# transistor-BSS806N.net
KiCad netlist of a schematic drawn in EAGLE
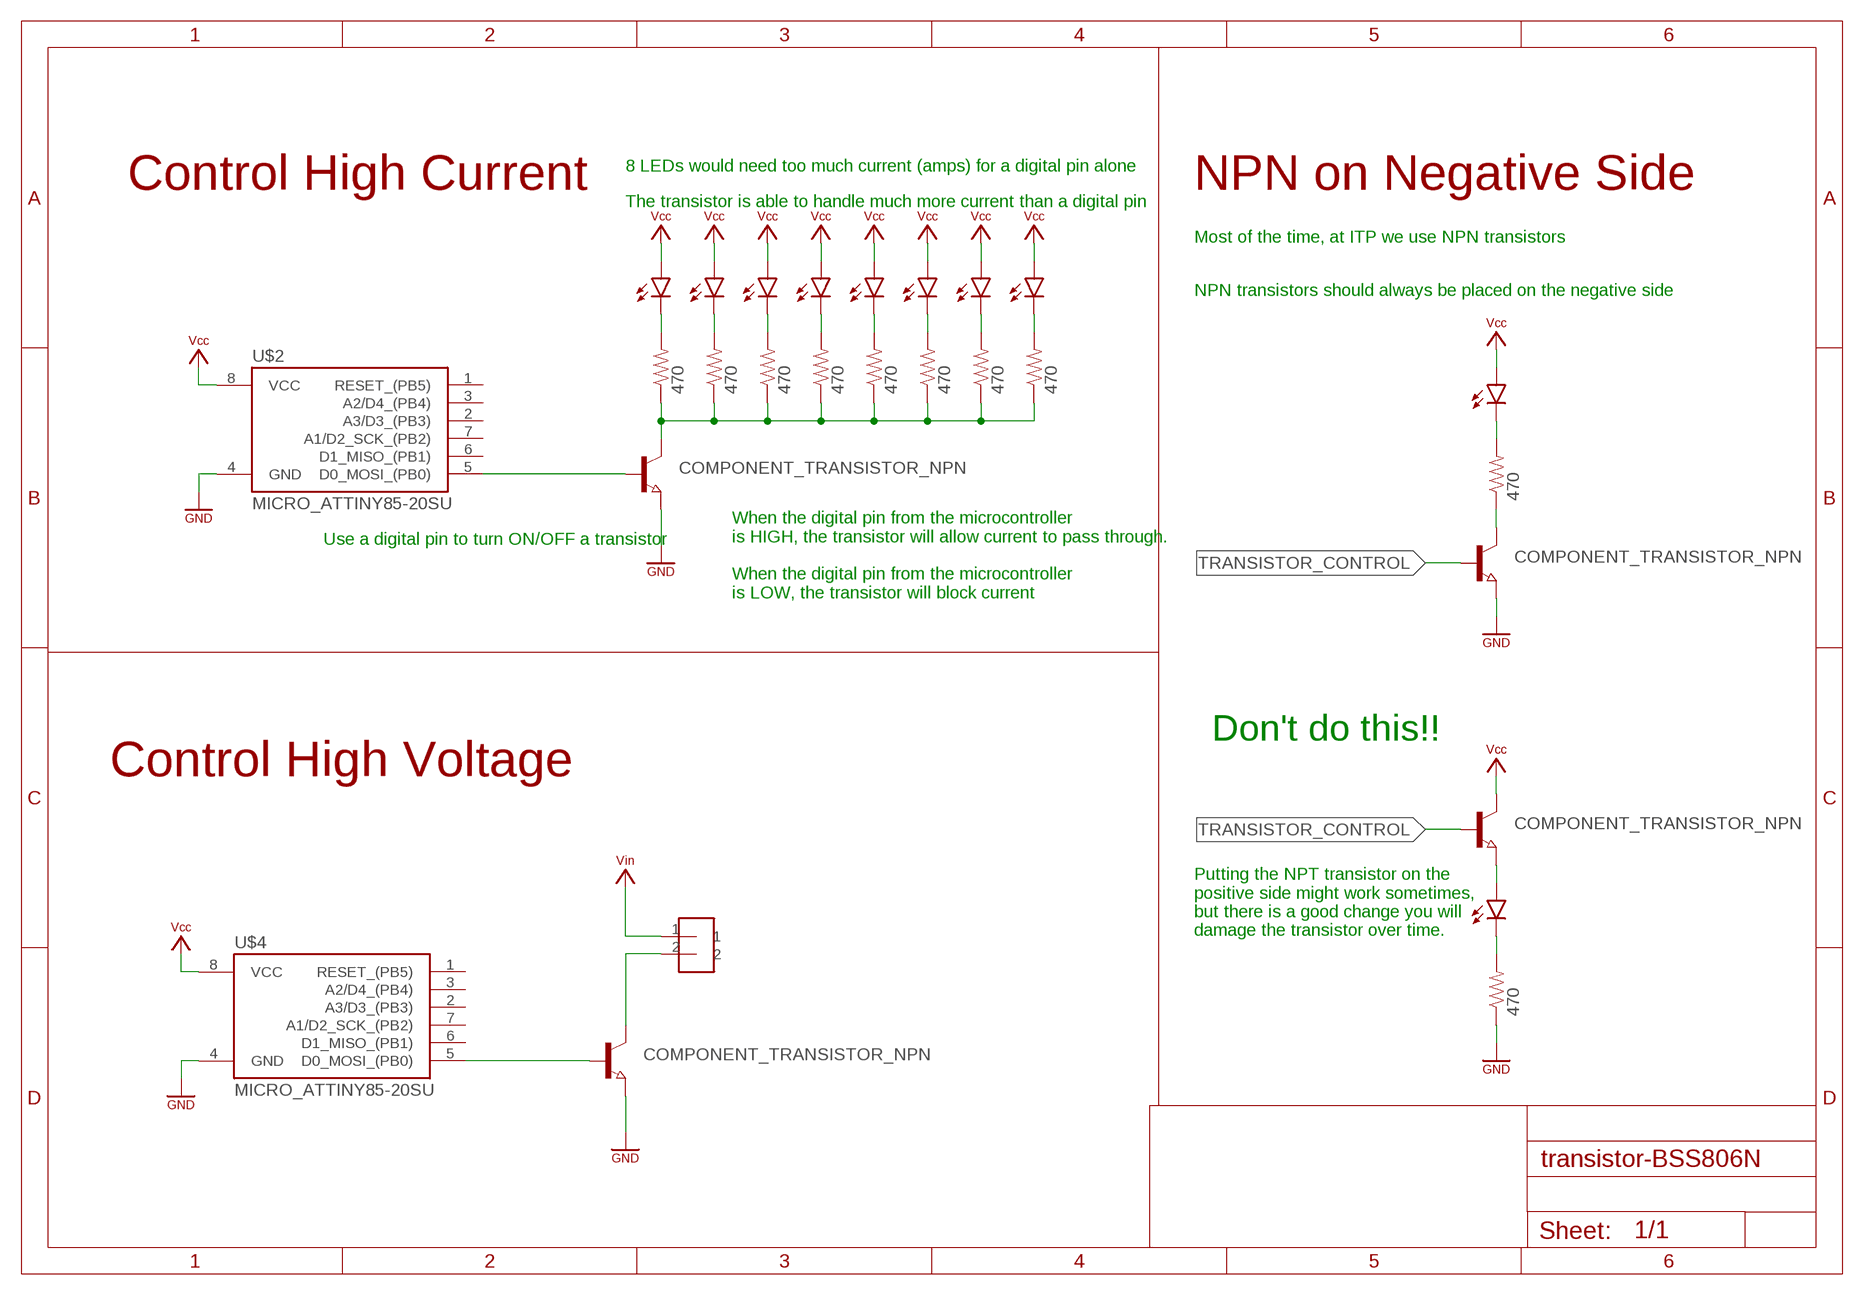
[diagram p0: schematic, sheet 1]

(export (version "E")
  (design (tool "Eeschema 10.0.6"))
  (components
    (comp (ref "LED1")
      (value "LED-0805")
      (footprint "eagle-import:CHIP-LED0805")
      (libsource (lib "eagle-import") (part "LED-0805"))
    )
    (comp (ref "LED2")
      (value "LED-0805")
      (footprint "eagle-import:CHIP-LED0805")
      (libsource (lib "eagle-import") (part "LED-0805"))
    )
    (comp (ref "LED3")
      (value "LED-0805")
      (footprint "eagle-import:CHIP-LED0805")
      (libsource (lib "eagle-import") (part "LED-0805"))
    )
    (comp (ref "LED4")
      (value "LED-0805")
      (footprint "eagle-import:CHIP-LED0805")
      (libsource (lib "eagle-import") (part "LED-0805"))
    )
    (comp (ref "LED5")
      (value "LED-0805")
      (footprint "eagle-import:CHIP-LED0805")
      (libsource (lib "eagle-import") (part "LED-0805"))
    )
    (comp (ref "LED6")
      (value "LED-0805")
      (footprint "eagle-import:CHIP-LED0805")
      (libsource (lib "eagle-import") (part "LED-0805"))
    )
    (comp (ref "LED7")
      (value "LED-0805")
      (footprint "eagle-import:CHIP-LED0805")
      (libsource (lib "eagle-import") (part "LED-0805"))
    )
    (comp (ref "LED8")
      (value "LED-0805")
      (footprint "eagle-import:CHIP-LED0805")
      (libsource (lib "eagle-import") (part "LED-0805"))
    )
    (comp (ref "LED9")
      (value "LED-0805")
      (footprint "eagle-import:CHIP-LED0805")
      (libsource (lib "eagle-import") (part "LED-0805"))
    )
    (comp (ref "LED10")
      (value "LED-0805")
      (footprint "eagle-import:CHIP-LED0805")
      (libsource (lib "eagle-import") (part "LED-0805"))
    )
    (comp (ref "R1")
      (value "470")
      (footprint "eagle-import:0805")
      (libsource (lib "eagle-import") (part "COMPONENT_RESISTOR-0805"))
    )
    (comp (ref "R2")
      (value "470")
      (footprint "eagle-import:0805")
      (libsource (lib "eagle-import") (part "COMPONENT_RESISTOR-0805"))
    )
    (comp (ref "R3")
      (value "470")
      (footprint "eagle-import:0805")
      (libsource (lib "eagle-import") (part "COMPONENT_RESISTOR-0805"))
    )
    (comp (ref "R4")
      (value "470")
      (footprint "eagle-import:0805")
      (libsource (lib "eagle-import") (part "COMPONENT_RESISTOR-0805"))
    )
    (comp (ref "R5")
      (value "470")
      (footprint "eagle-import:0805")
      (libsource (lib "eagle-import") (part "COMPONENT_RESISTOR-0805"))
    )
    (comp (ref "R6")
      (value "470")
      (footprint "eagle-import:0805")
      (libsource (lib "eagle-import") (part "COMPONENT_RESISTOR-0805"))
    )
    (comp (ref "R7")
      (value "470")
      (footprint "eagle-import:0805")
      (libsource (lib "eagle-import") (part "COMPONENT_RESISTOR-0805"))
    )
    (comp (ref "R8")
      (value "470")
      (footprint "eagle-import:0805")
      (libsource (lib "eagle-import") (part "COMPONENT_RESISTOR-0805"))
    )
    (comp (ref "R9")
      (value "470")
      (footprint "eagle-import:0805")
      (libsource (lib "eagle-import") (part "COMPONENT_RESISTOR-0805"))
    )
    (comp (ref "R10")
      (value "470")
      (footprint "eagle-import:0805")
      (libsource (lib "eagle-import") (part "COMPONENT_RESISTOR-0805"))
    )
    (comp (ref "U$1")
      (value "COMPONENT_TRANSISTOR_NPN")
      (footprint "eagle-import:SOT23")
      (libsource (lib "eagle-import") (part "COMPONENT_TRANSISTOR_NPN"))
    )
    (comp (ref "U$2")
      (value "MICRO_ATTINY85-20SU")
      (footprint "eagle-import:SOIC8")
      (libsource (lib "eagle-import") (part "MICRO_ATTINY85-20SU"))
    )
    (comp (ref "U$3")
      (value "COMPONENT_TRANSISTOR_NPN")
      (footprint "eagle-import:SOT23")
      (libsource (lib "eagle-import") (part "COMPONENT_TRANSISTOR_NPN"))
    )
    (comp (ref "U$4")
      (value "MICRO_ATTINY85-20SU")
      (footprint "eagle-import:SOIC8")
      (libsource (lib "eagle-import") (part "MICRO_ATTINY85-20SU"))
    )
    (comp (ref "U$5")
      (value "CONN_SCREW_TERMINAL")
      (footprint "eagle-import:691508110302")
      (libsource (lib "eagle-import") (part "CONN_SCREW_TERMINAL"))
    )
    (comp (ref "U$7")
      (value "COMPONENT_TRANSISTOR_NPN")
      (footprint "eagle-import:SOT23")
      (libsource (lib "eagle-import") (part "COMPONENT_TRANSISTOR_NPN"))
    )
    (comp (ref "U$8")
      (value "COMPONENT_TRANSISTOR_NPN")
      (footprint "eagle-import:SOT23")
      (libsource (lib "eagle-import") (part "COMPONENT_TRANSISTOR_NPN"))
    )
  )
  (nets
    (net (code "1") (name "Net-(LED1-PadC)") (class "Default")
      (node (ref "LED1") (pin "C") (pinfunction "C_C") (pintype "passive"))
      (node (ref "R1") (pin "2") (pinfunction "2_2") (pintype "passive"))
    )
    (net (code "2") (name "Net-(LED2-PadC)") (class "Default")
      (node (ref "LED2") (pin "C") (pinfunction "C_C") (pintype "passive"))
      (node (ref "R2") (pin "2") (pinfunction "2_2") (pintype "passive"))
    )
    (net (code "3") (name "Net-(LED3-PadC)") (class "Default")
      (node (ref "LED3") (pin "C") (pinfunction "C_C") (pintype "passive"))
      (node (ref "R3") (pin "2") (pinfunction "2_2") (pintype "passive"))
    )
    (net (code "4") (name "Net-(LED4-PadC)") (class "Default")
      (node (ref "LED4") (pin "C") (pinfunction "C_C") (pintype "passive"))
      (node (ref "R4") (pin "2") (pinfunction "2_2") (pintype "passive"))
    )
    (net (code "5") (name "Net-(LED5-PadC)") (class "Default")
      (node (ref "LED5") (pin "C") (pinfunction "C_C") (pintype "passive"))
      (node (ref "R5") (pin "2") (pinfunction "2_2") (pintype "passive"))
    )
    (net (code "6") (name "Net-(LED6-PadC)") (class "Default")
      (node (ref "LED6") (pin "C") (pinfunction "C_C") (pintype "passive"))
      (node (ref "R6") (pin "2") (pinfunction "2_2") (pintype "passive"))
    )
    (net (code "7") (name "Net-(LED7-PadC)") (class "Default")
      (node (ref "LED7") (pin "C") (pinfunction "C_C") (pintype "passive"))
      (node (ref "R7") (pin "2") (pinfunction "2_2") (pintype "passive"))
    )
    (net (code "8") (name "Net-(LED8-PadC)") (class "Default")
      (node (ref "LED8") (pin "C") (pinfunction "C_C") (pintype "passive"))
      (node (ref "R8") (pin "2") (pinfunction "2_2") (pintype "passive"))
    )
    (net (code "9") (name "Net-(LED9-PadC)") (class "Default")
      (node (ref "LED9") (pin "C") (pinfunction "C_C") (pintype "passive"))
      (node (ref "R9") (pin "2") (pinfunction "2_2") (pintype "passive"))
    )
    (net (code "10") (name "Net-(LED10-PadC)") (class "Default")
      (node (ref "LED10") (pin "C") (pinfunction "C_C") (pintype "passive"))
      (node (ref "R10") (pin "2") (pinfunction "2_2") (pintype "passive"))
    )
    (net (code "11") (name "Net-(U$1-B)") (class "Default")
      (node (ref "U$1") (pin "1") (pinfunction "B_1") (pintype "passive"))
      (node (ref "U$2") (pin "5") (pinfunction "D0_MOSI_(PB0)_5") (pintype "bidirectional"))
    )
    (net (code "12") (name "Net-(U$1-C)") (class "Default")
      (node (ref "R1") (pin "1") (pinfunction "1_1") (pintype "passive"))
      (node (ref "R2") (pin "1") (pinfunction "1_1") (pintype "passive"))
      (node (ref "R3") (pin "1") (pinfunction "1_1") (pintype "passive"))
      (node (ref "R4") (pin "1") (pinfunction "1_1") (pintype "passive"))
      (node (ref "R5") (pin "1") (pinfunction "1_1") (pintype "passive"))
      (node (ref "R6") (pin "1") (pinfunction "1_1") (pintype "passive"))
      (node (ref "R7") (pin "1") (pinfunction "1_1") (pintype "passive"))
      (node (ref "R8") (pin "1") (pinfunction "1_1") (pintype "passive"))
      (node (ref "U$1") (pin "3") (pinfunction "C_3") (pintype "passive"))
    )
    (net (code "13") (name "Net-(U$3-B)") (class "Default")
      (node (ref "U$3") (pin "1") (pinfunction "B_1") (pintype "passive"))
      (node (ref "U$4") (pin "5") (pinfunction "D0_MOSI_(PB0)_5") (pintype "bidirectional"))
    )
    (net (code "14") (name "Net-(U$3-C)") (class "Default")
      (node (ref "U$3") (pin "3") (pinfunction "C_3") (pintype "passive"))
      (node (ref "U$5") (pin "2") (pinfunction "2_2") (pintype "bidirectional"))
    )
    (net (code "15") (name "Net-(U$7-C)") (class "Default")
      (node (ref "R9") (pin "1") (pinfunction "1_1") (pintype "passive"))
      (node (ref "U$7") (pin "3") (pinfunction "C_3") (pintype "passive"))
    )
    (net (code "16") (name "Net-(U$8-E)") (class "Default")
      (node (ref "LED10") (pin "A") (pinfunction "A_A") (pintype "passive"))
      (node (ref "U$8") (pin "2") (pinfunction "E_2") (pintype "passive"))
    )
    (net (code "17") (name "SYMBOL_GND") (class "Default")
      (node (ref "R10") (pin "1") (pinfunction "1_1") (pintype "passive"))
      (node (ref "U$1") (pin "2") (pinfunction "E_2") (pintype "passive"))
      (node (ref "U$2") (pin "4") (pinfunction "GND_4") (pintype "power_in"))
      (node (ref "U$3") (pin "2") (pinfunction "E_2") (pintype "passive"))
      (node (ref "U$4") (pin "4") (pinfunction "GND_4") (pintype "power_in"))
      (node (ref "U$7") (pin "2") (pinfunction "E_2") (pintype "passive"))
    )
    (net (code "18") (name "SYMBOL_VCC") (class "Default")
      (node (ref "LED1") (pin "A") (pinfunction "A_A") (pintype "passive"))
      (node (ref "LED2") (pin "A") (pinfunction "A_A") (pintype "passive"))
      (node (ref "LED3") (pin "A") (pinfunction "A_A") (pintype "passive"))
      (node (ref "LED4") (pin "A") (pinfunction "A_A") (pintype "passive"))
      (node (ref "LED5") (pin "A") (pinfunction "A_A") (pintype "passive"))
      (node (ref "LED6") (pin "A") (pinfunction "A_A") (pintype "passive"))
      (node (ref "LED7") (pin "A") (pinfunction "A_A") (pintype "passive"))
      (node (ref "LED8") (pin "A") (pinfunction "A_A") (pintype "passive"))
      (node (ref "LED9") (pin "A") (pinfunction "A_A") (pintype "passive"))
      (node (ref "U$2") (pin "8") (pinfunction "VCC_8") (pintype "power_in"))
      (node (ref "U$4") (pin "8") (pinfunction "VCC_8") (pintype "power_in"))
      (node (ref "U$8") (pin "3") (pinfunction "C_3") (pintype "passive"))
    )
    (net (code "19") (name "SYMBOL_VIN") (class "Default")
      (node (ref "U$5") (pin "1") (pinfunction "1_1") (pintype "bidirectional"))
    )
    (net (code "20") (name "TRANSISTOR_CONTROL") (class "Default")
      (node (ref "U$7") (pin "1") (pinfunction "B_1") (pintype "passive"))
      (node (ref "U$8") (pin "1") (pinfunction "B_1") (pintype "passive"))
    )
    (net (code "21") (name "unconnected-(U$2-A1{slash}D2_SCK_(PB2)-Pad7)") (class "Default")
      (node (ref "U$2") (pin "7") (pinfunction "A1/D2_SCK_(PB2)_7") (pintype "bidirectional"))
    )
    (net (code "22") (name "unconnected-(U$2-A2{slash}D4_(PB4)-Pad3)") (class "Default")
      (node (ref "U$2") (pin "3") (pinfunction "A2/D4_(PB4)_3") (pintype "bidirectional"))
    )
    (net (code "23") (name "unconnected-(U$2-A3{slash}D3_(PB3)-Pad2)") (class "Default")
      (node (ref "U$2") (pin "2") (pinfunction "A3/D3_(PB3)_2") (pintype "bidirectional"))
    )
    (net (code "24") (name "unconnected-(U$2-D1_MISO_(PB1)-Pad6)") (class "Default")
      (node (ref "U$2") (pin "6") (pinfunction "D1_MISO_(PB1)_6") (pintype "bidirectional"))
    )
    (net (code "25") (name "unconnected-(U$2-RESET_(PB5)-Pad1)") (class "Default")
      (node (ref "U$2") (pin "1") (pinfunction "RESET_(PB5)_1") (pintype "bidirectional"))
    )
    (net (code "26") (name "unconnected-(U$4-A1{slash}D2_SCK_(PB2)-Pad7)") (class "Default")
      (node (ref "U$4") (pin "7") (pinfunction "A1/D2_SCK_(PB2)_7") (pintype "bidirectional"))
    )
    (net (code "27") (name "unconnected-(U$4-A2{slash}D4_(PB4)-Pad3)") (class "Default")
      (node (ref "U$4") (pin "3") (pinfunction "A2/D4_(PB4)_3") (pintype "bidirectional"))
    )
    (net (code "28") (name "unconnected-(U$4-A3{slash}D3_(PB3)-Pad2)") (class "Default")
      (node (ref "U$4") (pin "2") (pinfunction "A3/D3_(PB3)_2") (pintype "bidirectional"))
    )
    (net (code "29") (name "unconnected-(U$4-D1_MISO_(PB1)-Pad6)") (class "Default")
      (node (ref "U$4") (pin "6") (pinfunction "D1_MISO_(PB1)_6") (pintype "bidirectional"))
    )
    (net (code "30") (name "unconnected-(U$4-RESET_(PB5)-Pad1)") (class "Default")
      (node (ref "U$4") (pin "1") (pinfunction "RESET_(PB5)_1") (pintype "bidirectional"))
    )
  )
)
